# T07_-Schematic_V5.net
KiCad netlist of a schematic drawn in EAGLE
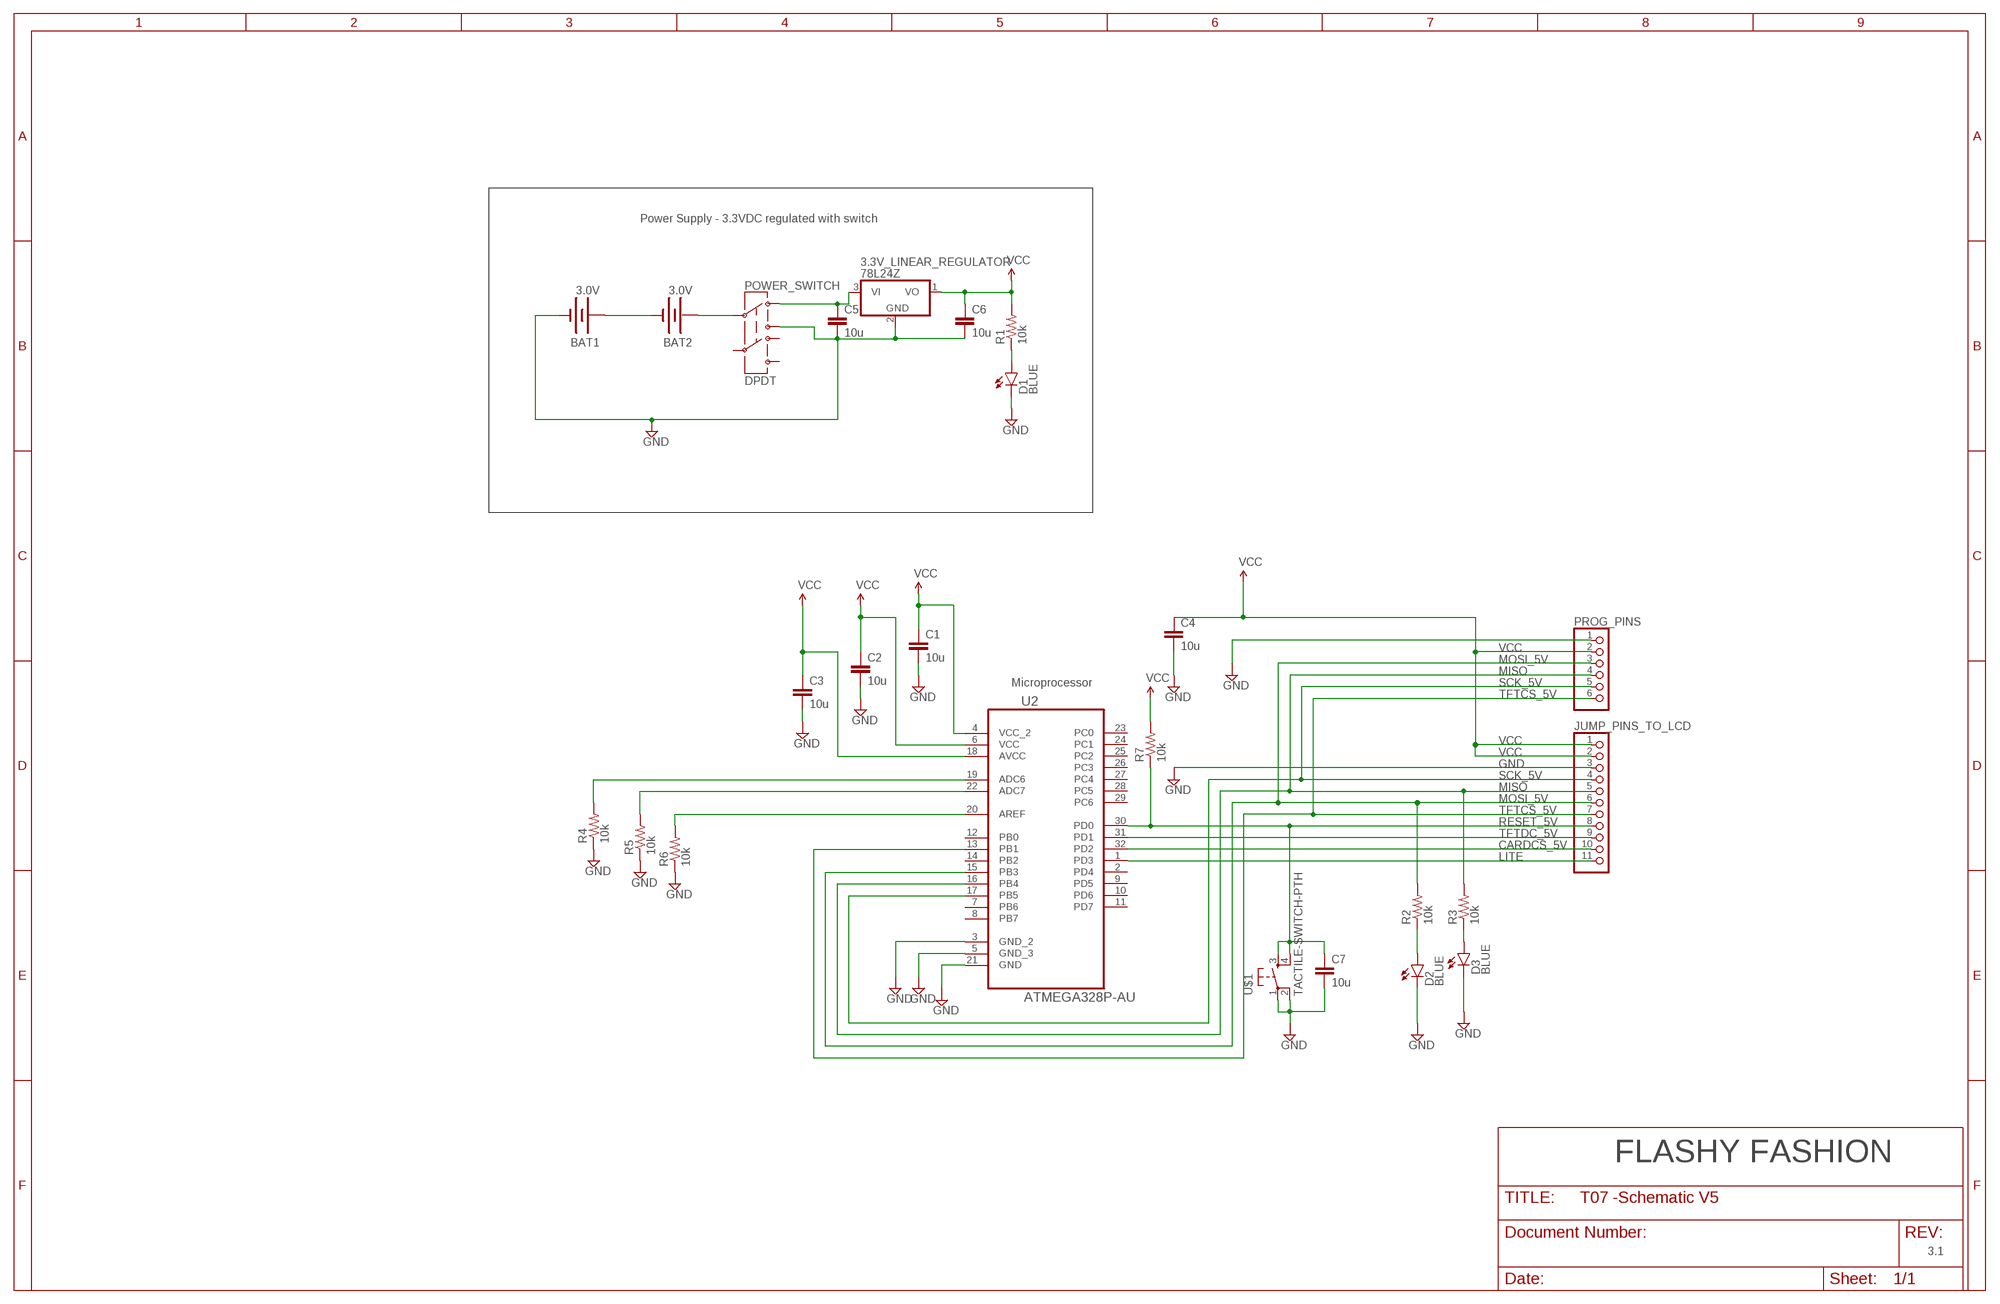
[diagram p0: schematic, sheet 1]

(export (version "E")
  (design (tool "Eeschema 10.0.6"))
  (components
    (comp (ref "3.3V_LINEAR_REGULATOR")
      (value "78L24Z")
      (footprint "eagle-import:TO92")
      (libsource (lib "eagle-import") (part "78ZL24"))
    )
    (comp (ref "BAT1")
      (value "3.0V")
      (footprint "eagle-import:BATTCON_245MM_PTH")
      (libsource (lib "eagle-import") (part "BATTERY245PTH"))
    )
    (comp (ref "BAT2")
      (value "3.0V")
      (footprint "eagle-import:BATTCON_245MM_PTH")
      (libsource (lib "eagle-import") (part "BATTERY245PTH"))
    )
    (comp (ref "C1")
      (value "10u")
      (footprint "eagle-import:1206")
      (libsource (lib "eagle-import") (part "CAP1206"))
    )
    (comp (ref "C2")
      (value "10u")
      (footprint "eagle-import:1206")
      (libsource (lib "eagle-import") (part "CAP1206"))
    )
    (comp (ref "C3")
      (value "10u")
      (footprint "eagle-import:1206")
      (libsource (lib "eagle-import") (part "CAP1206"))
    )
    (comp (ref "C4")
      (value "10u")
      (footprint "eagle-import:1206")
      (libsource (lib "eagle-import") (part "CAP1206"))
    )
    (comp (ref "C5")
      (value "10u")
      (footprint "eagle-import:1206")
      (libsource (lib "eagle-import") (part "CAP1206"))
    )
    (comp (ref "C6")
      (value "10u")
      (footprint "eagle-import:1206")
      (libsource (lib "eagle-import") (part "SparkFun-Passives_CAP1206"))
    )
    (comp (ref "C7")
      (value "10u")
      (footprint "eagle-import:1206")
      (libsource (lib "eagle-import") (part "CAP1206"))
    )
    (comp (ref "D1")
      (value "BLUE")
      (footprint "eagle-import:LED-1206")
      (libsource (lib "eagle-import") (part "LED-BLUE1206"))
    )
    (comp (ref "D2")
      (value "BLUE")
      (footprint "eagle-import:LED-1206")
      (libsource (lib "eagle-import") (part "LED-BLUE1206"))
    )
    (comp (ref "D3")
      (value "BLUE")
      (footprint "eagle-import:LED-1206")
      (libsource (lib "eagle-import") (part "LED-BLUE1206"))
    )
    (comp (ref "JUMP_PINS_TO_LCD")
      (value "HEADER-1X1176MIL")
      (footprint "eagle-import:1X11_ROUND_76")
      (libsource (lib "eagle-import") (part "HEADER-1X1176MIL"))
    )
    (comp (ref "POWER_SWITCH")
      (value "DPDT")
      (footprint "eagle-import:AYZ0202")
      (libsource (lib "eagle-import") (part "SWITCH-DPDTAYZ0202"))
    )
    (comp (ref "PROG_PINS")
      (value "PINHD-1X6-3.5MM")
      (footprint "eagle-import:1X06-3.5MM")
      (libsource (lib "eagle-import") (part "PINHD-1X6-3.5MM"))
    )
    (comp (ref "R1")
      (value "10k")
      (footprint "eagle-import:1206")
      (libsource (lib "eagle-import") (part "SparkFun-Resistors_RESISTOR1206"))
    )
    (comp (ref "R2")
      (value "10k")
      (footprint "eagle-import:1206")
      (libsource (lib "eagle-import") (part "SparkFun-Resistors_RESISTOR1206"))
    )
    (comp (ref "R3")
      (value "10k")
      (footprint "eagle-import:1206")
      (libsource (lib "eagle-import") (part "SparkFun-Resistors_RESISTOR1206"))
    )
    (comp (ref "R4")
      (value "10k")
      (footprint "eagle-import:1206")
      (libsource (lib "eagle-import") (part "SparkFun-Resistors_RESISTOR1206"))
    )
    (comp (ref "R5")
      (value "10k")
      (footprint "eagle-import:1206")
      (libsource (lib "eagle-import") (part "SparkFun-Resistors_RESISTOR1206"))
    )
    (comp (ref "R6")
      (value "10k")
      (footprint "eagle-import:1206")
      (libsource (lib "eagle-import") (part "SparkFun-Resistors_RESISTOR1206"))
    )
    (comp (ref "R7")
      (value "10k")
      (footprint "eagle-import:1206")
      (libsource (lib "eagle-import") (part "RESISTOR1206"))
    )
    (comp (ref "U$1")
      (value "TACTILE-SWITCH-PTH")
      (footprint "eagle-import:TAC-SWITCH-PTH")
      (libsource (lib "eagle-import") (part "TACTILE-SWITCH-PTH"))
    )
    (comp (ref "U2")
      (value "ATMEGA328P-AU")
      (footprint "eagle-import:QFP80P900X900X120-32N")
      (libsource (lib "eagle-import") (part "ATMEGA328P-AU"))
    )
  )
  (nets
    (net (code "1") (name "/CARDCS_5V") (class "Default")
      (node (ref "JUMP_PINS_TO_LCD") (pin "10") (pinfunction "10_10") (pintype "passive"))
      (node (ref "U2") (pin "32") (pinfunction "PD2_32") (pintype "bidirectional"))
    )
    (net (code "2") (name "/LITE") (class "Default")
      (node (ref "JUMP_PINS_TO_LCD") (pin "11") (pinfunction "11_11") (pintype "passive"))
      (node (ref "U2") (pin "1") (pinfunction "PD3_1") (pintype "bidirectional"))
    )
    (net (code "3") (name "/MISO") (class "Default")
      (node (ref "JUMP_PINS_TO_LCD") (pin "5") (pinfunction "5_5") (pintype "passive"))
      (node (ref "PROG_PINS") (pin "4") (pinfunction "4_4") (pintype "passive"))
      (node (ref "R3") (pin "2") (pinfunction "2_2") (pintype "passive"))
      (node (ref "U2") (pin "16") (pinfunction "PB4_16") (pintype "bidirectional"))
    )
    (net (code "4") (name "/MOSI_5V") (class "Default")
      (node (ref "JUMP_PINS_TO_LCD") (pin "6") (pinfunction "6_6") (pintype "passive"))
      (node (ref "PROG_PINS") (pin "3") (pinfunction "3_3") (pintype "passive"))
      (node (ref "R2") (pin "2") (pinfunction "2_2") (pintype "passive"))
      (node (ref "U2") (pin "15") (pinfunction "PB3_15") (pintype "bidirectional"))
    )
    (net (code "5") (name "/RESET_5V") (class "Default")
      (node (ref "C7") (pin "1") (pinfunction "1_1") (pintype "passive"))
      (node (ref "JUMP_PINS_TO_LCD") (pin "8") (pinfunction "8_8") (pintype "passive"))
      (node (ref "R7") (pin "1") (pinfunction "1_1") (pintype "passive"))
      (node (ref "U$1") (pin "3") (pinfunction "3_3") (pintype "passive"))
      (node (ref "U$1") (pin "4") (pinfunction "4_4") (pintype "passive"))
      (node (ref "U2") (pin "30") (pinfunction "PD0_30") (pintype "bidirectional"))
    )
    (net (code "6") (name "/SCK_5V") (class "Default")
      (node (ref "JUMP_PINS_TO_LCD") (pin "4") (pinfunction "4_4") (pintype "passive"))
      (node (ref "PROG_PINS") (pin "5") (pinfunction "5_5") (pintype "passive"))
      (node (ref "U2") (pin "17") (pinfunction "PB5_17") (pintype "bidirectional"))
    )
    (net (code "7") (name "/TFTCS_5V") (class "Default")
      (node (ref "JUMP_PINS_TO_LCD") (pin "7") (pinfunction "7_7") (pintype "passive"))
      (node (ref "PROG_PINS") (pin "6") (pinfunction "6_6") (pintype "passive"))
      (node (ref "U2") (pin "13") (pinfunction "PB1_13") (pintype "bidirectional"))
    )
    (net (code "8") (name "/TFTDC_5V") (class "Default")
      (node (ref "JUMP_PINS_TO_LCD") (pin "9") (pinfunction "9_9") (pintype "passive"))
      (node (ref "U2") (pin "31") (pinfunction "PD1_31") (pintype "bidirectional"))
    )
    (net (code "9") (name "GND") (class "Default")
      (node (ref "3.3V_LINEAR_REGULATOR") (pin "2") (pinfunction "GND_2") (pintype "passive"))
      (node (ref "BAT1") (pin "2") (pinfunction "-_2") (pintype "power_in"))
      (node (ref "C1") (pin "2") (pinfunction "2_2") (pintype "passive"))
      (node (ref "C2") (pin "2") (pinfunction "2_2") (pintype "passive"))
      (node (ref "C3") (pin "2") (pinfunction "2_2") (pintype "passive"))
      (node (ref "C4") (pin "2") (pinfunction "2_2") (pintype "passive"))
      (node (ref "C5") (pin "2") (pinfunction "2_2") (pintype "passive"))
      (node (ref "C6") (pin "2") (pinfunction "2_2") (pintype "passive"))
      (node (ref "C7") (pin "2") (pinfunction "2_2") (pintype "passive"))
      (node (ref "D1") (pin "C") (pinfunction "C_C") (pintype "passive"))
      (node (ref "D2") (pin "C") (pinfunction "C_C") (pintype "passive"))
      (node (ref "D3") (pin "C") (pinfunction "C_C") (pintype "passive"))
      (node (ref "JUMP_PINS_TO_LCD") (pin "3") (pinfunction "3_3") (pintype "passive"))
      (node (ref "POWER_SWITCH") (pin "3") (pinfunction "3_3") (pintype "bidirectional"))
      (node (ref "PROG_PINS") (pin "1") (pinfunction "1_1") (pintype "passive"))
      (node (ref "R4") (pin "1") (pinfunction "1_1") (pintype "passive"))
      (node (ref "R5") (pin "1") (pinfunction "1_1") (pintype "passive"))
      (node (ref "R6") (pin "1") (pinfunction "1_1") (pintype "passive"))
      (node (ref "U$1") (pin "1") (pinfunction "1_1") (pintype "passive"))
      (node (ref "U$1") (pin "2") (pinfunction "2_2") (pintype "passive"))
      (node (ref "U2") (pin "21") (pinfunction "GND_21") (pintype "passive"))
      (node (ref "U2") (pin "3") (pinfunction "GND_2_3") (pintype "passive"))
      (node (ref "U2") (pin "5") (pinfunction "GND_3_5") (pintype "passive"))
    )
    (net (code "10") (name "Net-(3.3V_LINEAR_REGULATOR-VI)") (class "Default")
      (node (ref "3.3V_LINEAR_REGULATOR") (pin "3") (pinfunction "VI_3") (pintype "input"))
      (node (ref "C5") (pin "1") (pinfunction "1_1") (pintype "passive"))
      (node (ref "POWER_SWITCH") (pin "1") (pinfunction "1_1") (pintype "bidirectional"))
    )
    (net (code "11") (name "Net-(BAT1-+)") (class "Default")
      (node (ref "BAT1") (pin "3") (pinfunction "+_3") (pintype "power_in"))
      (node (ref "BAT2") (pin "2") (pinfunction "-_2") (pintype "power_in"))
    )
    (net (code "12") (name "Net-(BAT2-+)") (class "Default")
      (node (ref "BAT2") (pin "3") (pinfunction "+_3") (pintype "power_in"))
      (node (ref "POWER_SWITCH") (pin "2") (pinfunction "2_2") (pintype "bidirectional"))
    )
    (net (code "13") (name "Net-(D1-PadA)") (class "Default")
      (node (ref "D1") (pin "A") (pinfunction "A_A") (pintype "passive"))
      (node (ref "R1") (pin "1") (pinfunction "1_1") (pintype "passive"))
    )
    (net (code "14") (name "Net-(D2-PadA)") (class "Default")
      (node (ref "D2") (pin "A") (pinfunction "A_A") (pintype "passive"))
      (node (ref "R2") (pin "1") (pinfunction "1_1") (pintype "passive"))
    )
    (net (code "15") (name "Net-(D3-PadA)") (class "Default")
      (node (ref "D3") (pin "A") (pinfunction "A_A") (pintype "passive"))
      (node (ref "R3") (pin "1") (pinfunction "1_1") (pintype "passive"))
    )
    (net (code "16") (name "Net-(U2-ADC6)") (class "Default")
      (node (ref "R4") (pin "2") (pinfunction "2_2") (pintype "passive"))
      (node (ref "U2") (pin "19") (pinfunction "ADC6_19") (pintype "input"))
    )
    (net (code "17") (name "Net-(U2-ADC7)") (class "Default")
      (node (ref "R5") (pin "2") (pinfunction "2_2") (pintype "passive"))
      (node (ref "U2") (pin "22") (pinfunction "ADC7_22") (pintype "input"))
    )
    (net (code "18") (name "Net-(U2-AREF)") (class "Default")
      (node (ref "R6") (pin "2") (pinfunction "2_2") (pintype "passive"))
      (node (ref "U2") (pin "20") (pinfunction "AREF_20") (pintype "input"))
    )
    (net (code "19") (name "VCC") (class "Default")
      (node (ref "3.3V_LINEAR_REGULATOR") (pin "1") (pinfunction "VO_1") (pintype "passive"))
      (node (ref "C1") (pin "1") (pinfunction "1_1") (pintype "passive"))
      (node (ref "C2") (pin "1") (pinfunction "1_1") (pintype "passive"))
      (node (ref "C3") (pin "1") (pinfunction "1_1") (pintype "passive"))
      (node (ref "C4") (pin "1") (pinfunction "1_1") (pintype "passive"))
      (node (ref "C6") (pin "1") (pinfunction "1_1") (pintype "passive"))
      (node (ref "JUMP_PINS_TO_LCD") (pin "1") (pinfunction "1_1") (pintype "passive"))
      (node (ref "JUMP_PINS_TO_LCD") (pin "2") (pinfunction "2_2") (pintype "passive"))
      (node (ref "PROG_PINS") (pin "2") (pinfunction "2_2") (pintype "passive"))
      (node (ref "R1") (pin "2") (pinfunction "2_2") (pintype "passive"))
      (node (ref "R7") (pin "2") (pinfunction "2_2") (pintype "passive"))
      (node (ref "U2") (pin "18") (pinfunction "AVCC_18") (pintype "power_in"))
      (node (ref "U2") (pin "4") (pinfunction "VCC_2_4") (pintype "power_in"))
      (node (ref "U2") (pin "6") (pinfunction "VCC_6") (pintype "power_in"))
    )
    (net (code "20") (name "unconnected-(POWER_SWITCH-Pad4)") (class "Default")
      (node (ref "POWER_SWITCH") (pin "4") (pinfunction "4_4") (pintype "bidirectional"))
    )
    (net (code "21") (name "unconnected-(POWER_SWITCH-Pad5)") (class "Default")
      (node (ref "POWER_SWITCH") (pin "5") (pinfunction "5_5") (pintype "bidirectional"))
    )
    (net (code "22") (name "unconnected-(POWER_SWITCH-Pad6)") (class "Default")
      (node (ref "POWER_SWITCH") (pin "6") (pinfunction "6_6") (pintype "bidirectional"))
    )
    (net (code "23") (name "unconnected-(U2-PB0-Pad12)") (class "Default")
      (node (ref "U2") (pin "12") (pinfunction "PB0_12") (pintype "bidirectional"))
    )
    (net (code "24") (name "unconnected-(U2-PB2-Pad14)") (class "Default")
      (node (ref "U2") (pin "14") (pinfunction "PB2_14") (pintype "bidirectional"))
    )
    (net (code "25") (name "unconnected-(U2-PB6-Pad7)") (class "Default")
      (node (ref "U2") (pin "7") (pinfunction "PB6_7") (pintype "bidirectional"))
    )
    (net (code "26") (name "unconnected-(U2-PB7-Pad8)") (class "Default")
      (node (ref "U2") (pin "8") (pinfunction "PB7_8") (pintype "bidirectional"))
    )
    (net (code "27") (name "unconnected-(U2-PC0-Pad23)") (class "Default")
      (node (ref "U2") (pin "23") (pinfunction "PC0_23") (pintype "bidirectional"))
    )
    (net (code "28") (name "unconnected-(U2-PC1-Pad24)") (class "Default")
      (node (ref "U2") (pin "24") (pinfunction "PC1_24") (pintype "bidirectional"))
    )
    (net (code "29") (name "unconnected-(U2-PC2-Pad25)") (class "Default")
      (node (ref "U2") (pin "25") (pinfunction "PC2_25") (pintype "bidirectional"))
    )
    (net (code "30") (name "unconnected-(U2-PC3-Pad26)") (class "Default")
      (node (ref "U2") (pin "26") (pinfunction "PC3_26") (pintype "bidirectional"))
    )
    (net (code "31") (name "unconnected-(U2-PC4-Pad27)") (class "Default")
      (node (ref "U2") (pin "27") (pinfunction "PC4_27") (pintype "bidirectional"))
    )
    (net (code "32") (name "unconnected-(U2-PC5-Pad28)") (class "Default")
      (node (ref "U2") (pin "28") (pinfunction "PC5_28") (pintype "bidirectional"))
    )
    (net (code "33") (name "unconnected-(U2-PC6-Pad29)") (class "Default")
      (node (ref "U2") (pin "29") (pinfunction "PC6_29") (pintype "bidirectional"))
    )
    (net (code "34") (name "unconnected-(U2-PD4-Pad2)") (class "Default")
      (node (ref "U2") (pin "2") (pinfunction "PD4_2") (pintype "bidirectional"))
    )
    (net (code "35") (name "unconnected-(U2-PD5-Pad9)") (class "Default")
      (node (ref "U2") (pin "9") (pinfunction "PD5_9") (pintype "bidirectional"))
    )
    (net (code "36") (name "unconnected-(U2-PD6-Pad10)") (class "Default")
      (node (ref "U2") (pin "10") (pinfunction "PD6_10") (pintype "bidirectional"))
    )
    (net (code "37") (name "unconnected-(U2-PD7-Pad11)") (class "Default")
      (node (ref "U2") (pin "11") (pinfunction "PD7_11") (pintype "bidirectional"))
    )
  )
)
